# Waveform_Generator_Board.net
KiCad netlist of a schematic drawn in EAGLE
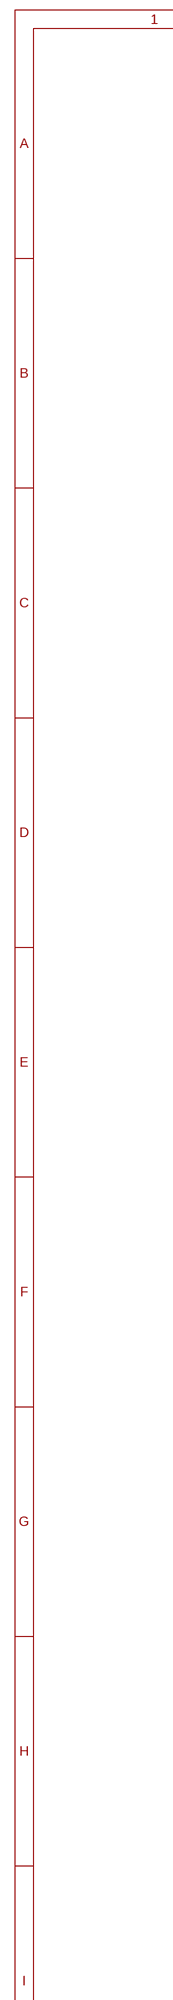
[diagram p0: schematic, sheet 1, part 1 of 2]
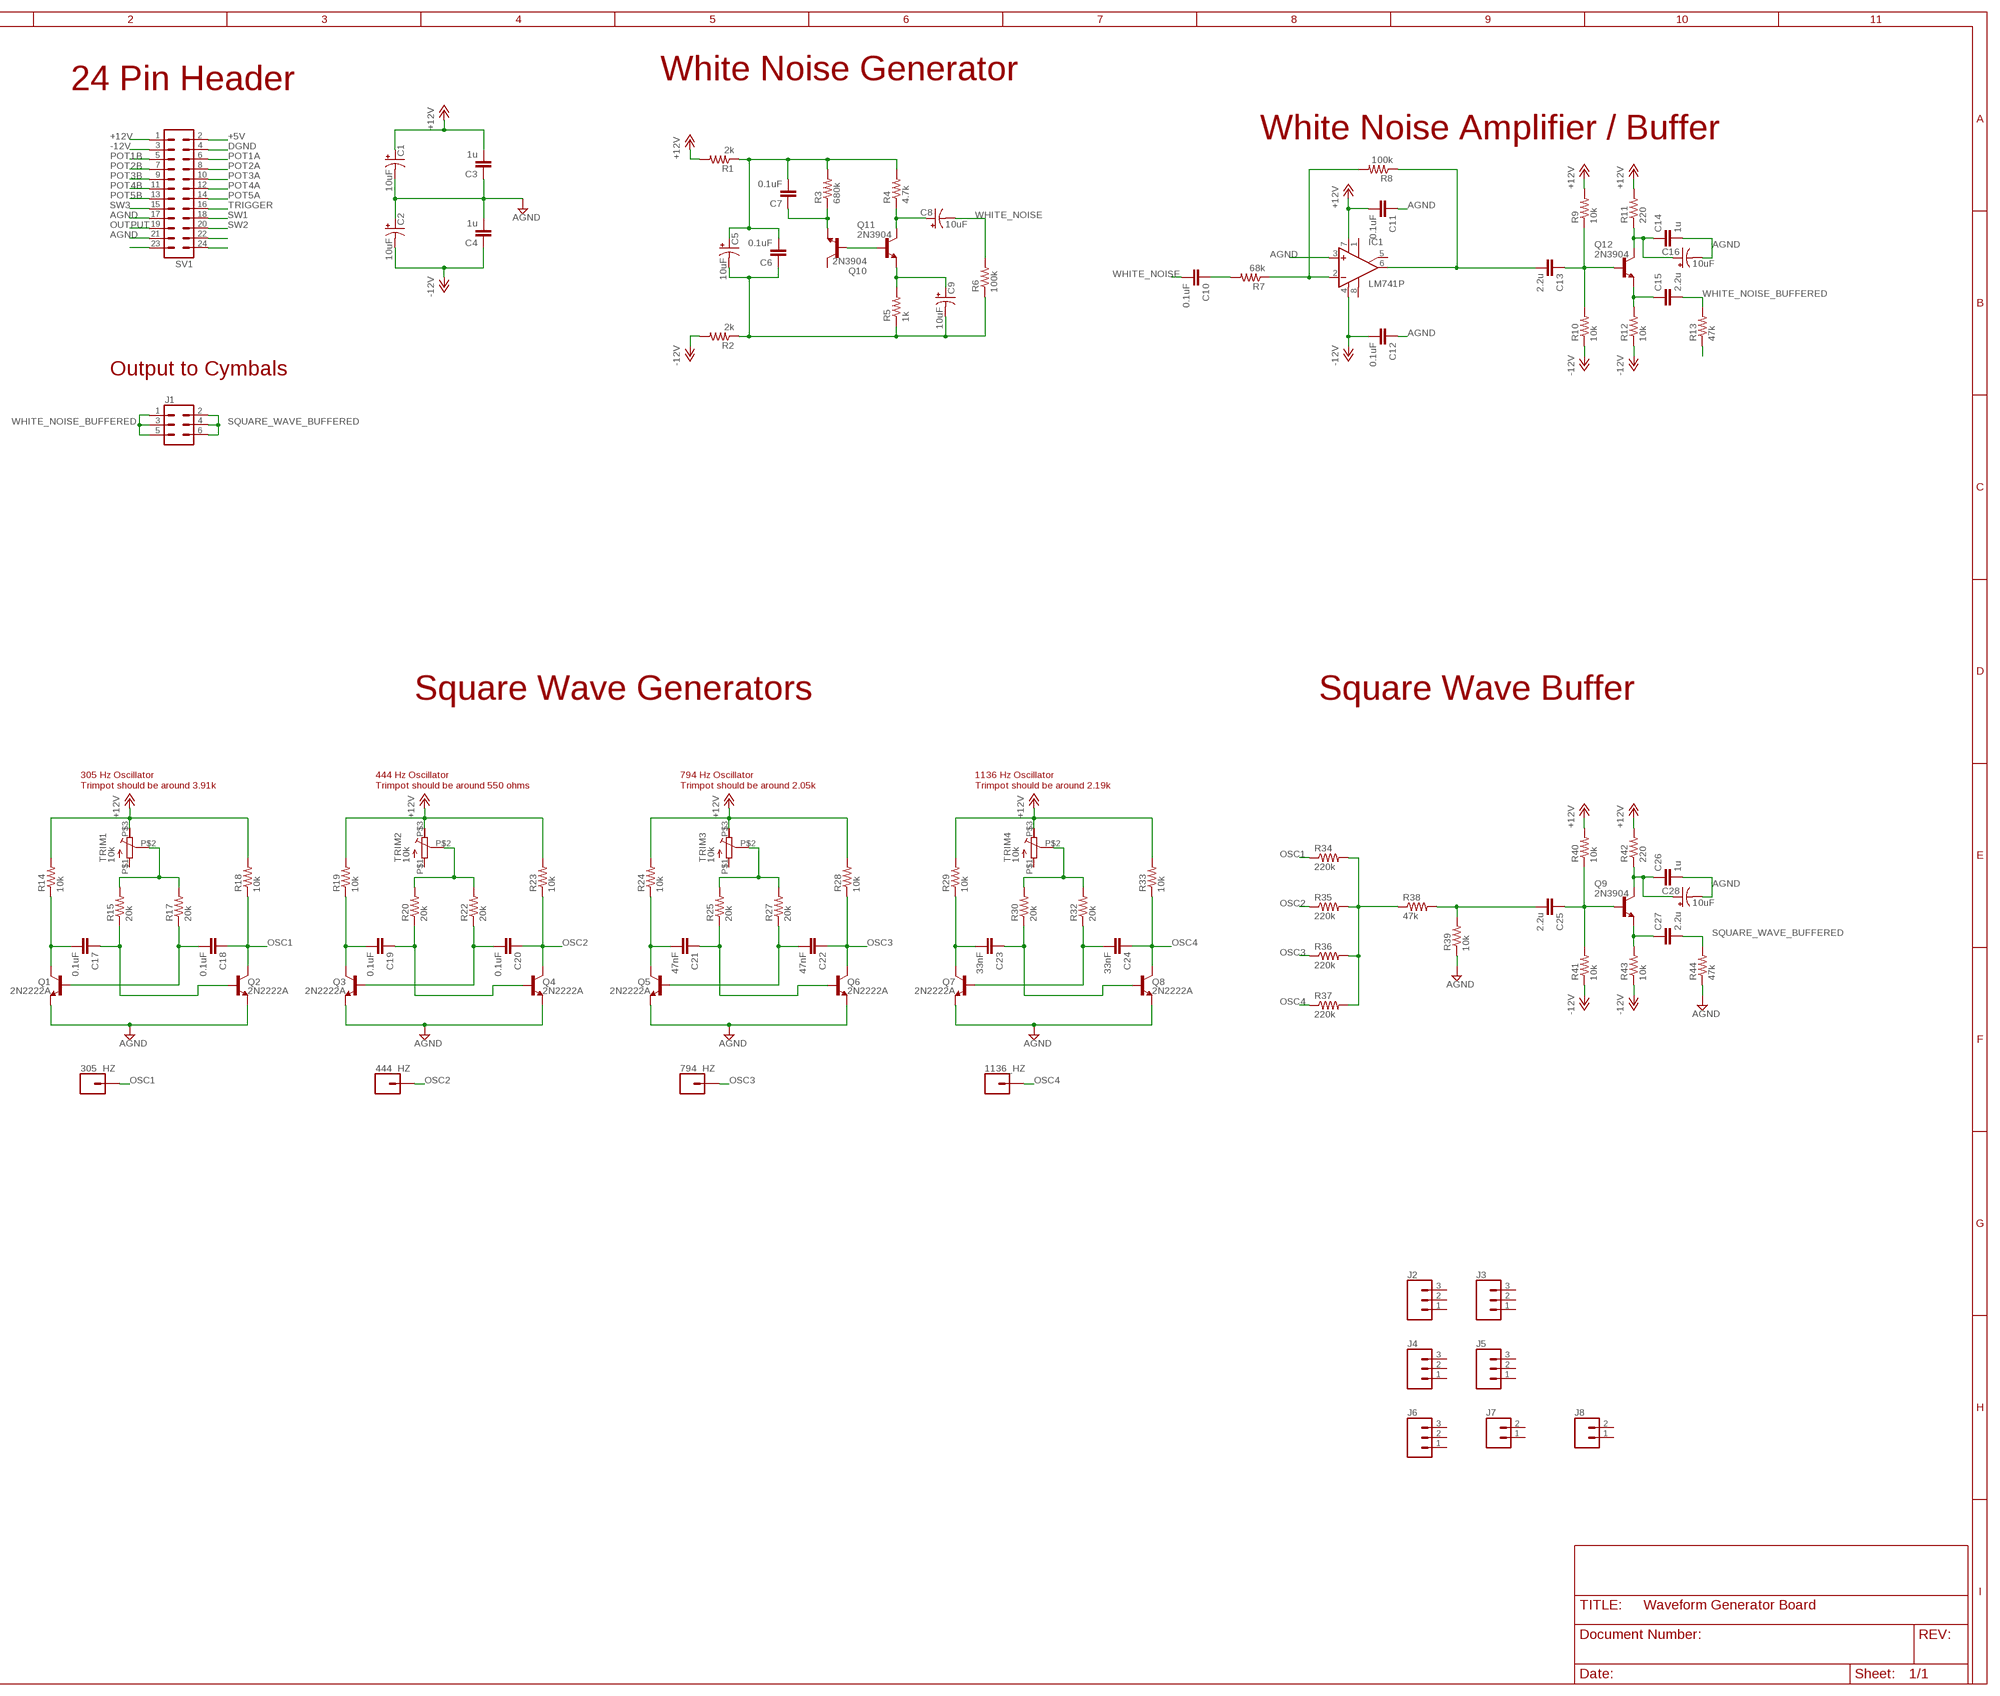
[diagram p1: schematic, sheet 1, part 2 of 2]

(export (version "E")
  (design (tool "Eeschema 10.0.6"))
  (components
    (comp (ref "305_HZ")
      (value "CONN_01PTH_NO_SILK_KIT")
      (footprint "eagle-import:1X01NS_KIT")
      (libsource (lib "eagle-import") (part "CONN_01PTH_NO_SILK_KIT"))
    )
    (comp (ref "444_HZ")
      (value "CONN_01PTH_NO_SILK_KIT")
      (footprint "eagle-import:1X01NS_KIT")
      (libsource (lib "eagle-import") (part "CONN_01PTH_NO_SILK_KIT"))
    )
    (comp (ref "794_HZ")
      (value "CONN_01PTH_NO_SILK_KIT")
      (footprint "eagle-import:1X01NS_KIT")
      (libsource (lib "eagle-import") (part "CONN_01PTH_NO_SILK_KIT"))
    )
    (comp (ref "1136_HZ")
      (value "CONN_01PTH_NO_SILK_KIT")
      (footprint "eagle-import:1X01NS_KIT")
      (libsource (lib "eagle-import") (part "CONN_01PTH_NO_SILK_KIT"))
    )
    (comp (ref "C1")
      (value "10uF")
      (footprint "eagle-import:E2,5-6")
      (libsource (lib "eagle-import") (part "CPOL-USE2.5-6"))
    )
    (comp (ref "C2")
      (value "10uF")
      (footprint "eagle-import:E2,5-6")
      (libsource (lib "eagle-import") (part "CPOL-USE2.5-6"))
    )
    (comp (ref "C3")
      (value "1u")
      (footprint "eagle-import:C050-024X044")
      (libsource (lib "eagle-import") (part "C-EU050-024X044"))
    )
    (comp (ref "C4")
      (value "1u")
      (footprint "eagle-import:C050-024X044")
      (libsource (lib "eagle-import") (part "C-EU050-024X044"))
    )
    (comp (ref "C5")
      (value "10uF")
      (footprint "eagle-import:E2,5-6")
      (libsource (lib "eagle-import") (part "CPOL-USE2.5-6"))
    )
    (comp (ref "C6")
      (value "0.1uF")
      (footprint "eagle-import:C050-024X044")
      (libsource (lib "eagle-import") (part "C-EU050-024X044"))
    )
    (comp (ref "C7")
      (value "0.1uF")
      (footprint "eagle-import:C050-024X044")
      (libsource (lib "eagle-import") (part "C-EU050-024X044"))
    )
    (comp (ref "C8")
      (value "10uF")
      (footprint "eagle-import:E2,5-6")
      (libsource (lib "eagle-import") (part "CPOL-USE2.5-6"))
    )
    (comp (ref "C9")
      (value "10uF")
      (footprint "eagle-import:E2,5-6")
      (libsource (lib "eagle-import") (part "CPOL-USE2.5-6"))
    )
    (comp (ref "C10")
      (value "0.1uF")
      (footprint "eagle-import:C050-024X044")
      (libsource (lib "eagle-import") (part "C-EU050-024X044"))
    )
    (comp (ref "C11")
      (value "0.1uF")
      (footprint "eagle-import:C050-024X044")
      (libsource (lib "eagle-import") (part "C-EU050-024X044"))
    )
    (comp (ref "C12")
      (value "0.1uF")
      (footprint "eagle-import:C050-024X044")
      (libsource (lib "eagle-import") (part "C-EU050-024X044"))
    )
    (comp (ref "C13")
      (value "2.2u")
      (footprint "eagle-import:C050-024X044")
      (libsource (lib "eagle-import") (part "C-EU050-024X044"))
    )
    (comp (ref "C14")
      (value "1u")
      (footprint "eagle-import:C050-024X044")
      (libsource (lib "eagle-import") (part "C-EU050-024X044"))
    )
    (comp (ref "C15")
      (value "2.2u")
      (footprint "eagle-import:C050-024X044")
      (libsource (lib "eagle-import") (part "C-EU050-024X044"))
    )
    (comp (ref "C16")
      (value "10uF")
      (footprint "eagle-import:E2,5-6")
      (libsource (lib "eagle-import") (part "CPOL-USE2.5-6"))
    )
    (comp (ref "C17")
      (value "0.1uF")
      (footprint "eagle-import:C050-024X044")
      (libsource (lib "eagle-import") (part "C-EU050-024X044"))
    )
    (comp (ref "C18")
      (value "0.1uF")
      (footprint "eagle-import:C050-024X044")
      (libsource (lib "eagle-import") (part "C-EU050-024X044"))
    )
    (comp (ref "C19")
      (value "0.1uF")
      (footprint "eagle-import:C050-024X044")
      (libsource (lib "eagle-import") (part "C-EU050-024X044"))
    )
    (comp (ref "C20")
      (value "0.1uF")
      (footprint "eagle-import:C050-024X044")
      (libsource (lib "eagle-import") (part "C-EU050-024X044"))
    )
    (comp (ref "C21")
      (value "47nF")
      (footprint "eagle-import:C050-024X044")
      (libsource (lib "eagle-import") (part "C-EU050-024X044"))
    )
    (comp (ref "C22")
      (value "47nF")
      (footprint "eagle-import:C050-024X044")
      (libsource (lib "eagle-import") (part "C-EU050-024X044"))
    )
    (comp (ref "C23")
      (value "33nF")
      (footprint "eagle-import:C050-024X044")
      (libsource (lib "eagle-import") (part "C-EU050-024X044"))
    )
    (comp (ref "C24")
      (value "33nF")
      (footprint "eagle-import:C050-024X044")
      (libsource (lib "eagle-import") (part "C-EU050-024X044"))
    )
    (comp (ref "C25")
      (value "2.2u")
      (footprint "eagle-import:C050-024X044")
      (libsource (lib "eagle-import") (part "C-EU050-024X044"))
    )
    (comp (ref "C26")
      (value "1u")
      (footprint "eagle-import:C050-024X044")
      (libsource (lib "eagle-import") (part "C-EU050-024X044"))
    )
    (comp (ref "C27")
      (value "2.2u")
      (footprint "eagle-import:C050-024X044")
      (libsource (lib "eagle-import") (part "C-EU050-024X044"))
    )
    (comp (ref "C28")
      (value "10uF")
      (footprint "eagle-import:E2,5-6")
      (libsource (lib "eagle-import") (part "CPOL-USE2.5-6"))
    )
    (comp (ref "IC1")
      (value "LM741P")
      (footprint "eagle-import:DIL08")
      (libsource (lib "eagle-import") (part "741PLM"))
    )
    (comp (ref "J1")
      (value "CONN_03X2NO_SILK")
      (footprint "eagle-import:2X3-NS")
      (libsource (lib "eagle-import") (part "CONN_03X2NO_SILK"))
    )
    (comp (ref "J2")
      (value "CONN_031X03_NO_SILK")
      (footprint "eagle-import:1X03_NO_SILK")
      (libsource (lib "eagle-import") (part "CONN_031X03_NO_SILK"))
    )
    (comp (ref "J3")
      (value "CONN_031X03_NO_SILK")
      (footprint "eagle-import:1X03_NO_SILK")
      (libsource (lib "eagle-import") (part "CONN_031X03_NO_SILK"))
    )
    (comp (ref "J4")
      (value "CONN_031X03_NO_SILK")
      (footprint "eagle-import:1X03_NO_SILK")
      (libsource (lib "eagle-import") (part "CONN_031X03_NO_SILK"))
    )
    (comp (ref "J5")
      (value "CONN_031X03_NO_SILK")
      (footprint "eagle-import:1X03_NO_SILK")
      (libsource (lib "eagle-import") (part "CONN_031X03_NO_SILK"))
    )
    (comp (ref "J6")
      (value "CONN_031X03_NO_SILK")
      (footprint "eagle-import:1X03_NO_SILK")
      (libsource (lib "eagle-import") (part "CONN_031X03_NO_SILK"))
    )
    (comp (ref "J7")
      (value "CONN_021X02_NO_SILK")
      (footprint "eagle-import:1X02_NO_SILK")
      (libsource (lib "eagle-import") (part "CONN_021X02_NO_SILK"))
    )
    (comp (ref "J8")
      (value "CONN_021X02_NO_SILK")
      (footprint "eagle-import:1X02_NO_SILK")
      (libsource (lib "eagle-import") (part "CONN_021X02_NO_SILK"))
    )
    (comp (ref "Q1")
      (value "2N2222A")
      (footprint "eagle-import:TO-92")
      (libsource (lib "eagle-import") (part "TRANS_NPN-P2N2222A"))
    )
    (comp (ref "Q2")
      (value "2N2222A")
      (footprint "eagle-import:TO-92")
      (libsource (lib "eagle-import") (part "TRANS_NPN-P2N2222A"))
    )
    (comp (ref "Q3")
      (value "2N2222A")
      (footprint "eagle-import:TO-92")
      (libsource (lib "eagle-import") (part "TRANS_NPN-P2N2222A"))
    )
    (comp (ref "Q4")
      (value "2N2222A")
      (footprint "eagle-import:TO-92")
      (libsource (lib "eagle-import") (part "TRANS_NPN-P2N2222A"))
    )
    (comp (ref "Q5")
      (value "2N2222A")
      (footprint "eagle-import:TO-92")
      (libsource (lib "eagle-import") (part "TRANS_NPN-P2N2222A"))
    )
    (comp (ref "Q6")
      (value "2N2222A")
      (footprint "eagle-import:TO-92")
      (libsource (lib "eagle-import") (part "TRANS_NPN-P2N2222A"))
    )
    (comp (ref "Q7")
      (value "2N2222A")
      (footprint "eagle-import:TO-92")
      (libsource (lib "eagle-import") (part "TRANS_NPN-P2N2222A"))
    )
    (comp (ref "Q8")
      (value "2N2222A")
      (footprint "eagle-import:TO-92")
      (libsource (lib "eagle-import") (part "TRANS_NPN-P2N2222A"))
    )
    (comp (ref "Q9")
      (value "2N3904")
      (footprint "eagle-import:TO92")
      (libsource (lib "eagle-import") (part "2N3904"))
    )
    (comp (ref "Q10")
      (value "2N3904")
      (footprint "eagle-import:TO92")
      (libsource (lib "eagle-import") (part "2N3904"))
    )
    (comp (ref "Q11")
      (value "2N3904")
      (footprint "eagle-import:TO92")
      (libsource (lib "eagle-import") (part "2N3904"))
    )
    (comp (ref "Q12")
      (value "2N3904")
      (footprint "eagle-import:TO92")
      (libsource (lib "eagle-import") (part "2N3904"))
    )
    (comp (ref "R1")
      (value "2k")
      (footprint "eagle-import:0207_7")
      (libsource (lib "eagle-import") (part "R-US_0207/7"))
    )
    (comp (ref "R2")
      (value "2k")
      (footprint "eagle-import:0207_7")
      (libsource (lib "eagle-import") (part "R-US_0207/7"))
    )
    (comp (ref "R3")
      (value "680k")
      (footprint "eagle-import:0207_7")
      (libsource (lib "eagle-import") (part "R-US_0207/7"))
    )
    (comp (ref "R4")
      (value "4.7k")
      (footprint "eagle-import:0207_7")
      (libsource (lib "eagle-import") (part "R-US_0207/7"))
    )
    (comp (ref "R5")
      (value "1k")
      (footprint "eagle-import:0207_7")
      (libsource (lib "eagle-import") (part "R-US_0207/7"))
    )
    (comp (ref "R6")
      (value "100k")
      (footprint "eagle-import:0207_7")
      (libsource (lib "eagle-import") (part "R-US_0207/7"))
    )
    (comp (ref "R7")
      (value "68k")
      (footprint "eagle-import:0207_7")
      (libsource (lib "eagle-import") (part "R-US_0207/7"))
    )
    (comp (ref "R8")
      (value "100k")
      (footprint "eagle-import:0207_7")
      (libsource (lib "eagle-import") (part "R-US_0207/7"))
    )
    (comp (ref "R9")
      (value "10k")
      (footprint "eagle-import:0207_7")
      (libsource (lib "eagle-import") (part "R-US_0207/7"))
    )
    (comp (ref "R10")
      (value "10k")
      (footprint "eagle-import:0207_7")
      (libsource (lib "eagle-import") (part "R-US_0207/7"))
    )
    (comp (ref "R11")
      (value "220")
      (footprint "eagle-import:0207_7")
      (libsource (lib "eagle-import") (part "R-US_0207/7"))
    )
    (comp (ref "R12")
      (value "10k")
      (footprint "eagle-import:0207_7")
      (libsource (lib "eagle-import") (part "R-US_0207/7"))
    )
    (comp (ref "R13")
      (value "47k")
      (footprint "eagle-import:0207_7")
      (libsource (lib "eagle-import") (part "R-US_0207/7"))
    )
    (comp (ref "R14")
      (value "10k")
      (footprint "eagle-import:0207_7")
      (libsource (lib "eagle-import") (part "R-US_0207/7"))
    )
    (comp (ref "R15")
      (value "20k")
      (footprint "eagle-import:0207_7")
      (libsource (lib "eagle-import") (part "R-US_0207/7"))
    )
    (comp (ref "R17")
      (value "20k")
      (footprint "eagle-import:0207_7")
      (libsource (lib "eagle-import") (part "R-US_0207/7"))
    )
    (comp (ref "R18")
      (value "10k")
      (footprint "eagle-import:0207_7")
      (libsource (lib "eagle-import") (part "R-US_0207/7"))
    )
    (comp (ref "R19")
      (value "10k")
      (footprint "eagle-import:0207_7")
      (libsource (lib "eagle-import") (part "R-US_0207/7"))
    )
    (comp (ref "R20")
      (value "20k")
      (footprint "eagle-import:0207_7")
      (libsource (lib "eagle-import") (part "R-US_0207/7"))
    )
    (comp (ref "R22")
      (value "20k")
      (footprint "eagle-import:0207_7")
      (libsource (lib "eagle-import") (part "R-US_0207/7"))
    )
    (comp (ref "R23")
      (value "10k")
      (footprint "eagle-import:0207_7")
      (libsource (lib "eagle-import") (part "R-US_0207/7"))
    )
    (comp (ref "R24")
      (value "10k")
      (footprint "eagle-import:0207_7")
      (libsource (lib "eagle-import") (part "R-US_0207/7"))
    )
    (comp (ref "R25")
      (value "20k")
      (footprint "eagle-import:0207_7")
      (libsource (lib "eagle-import") (part "R-US_0207/7"))
    )
    (comp (ref "R27")
      (value "20k")
      (footprint "eagle-import:0207_7")
      (libsource (lib "eagle-import") (part "R-US_0207/7"))
    )
    (comp (ref "R28")
      (value "10k")
      (footprint "eagle-import:0207_7")
      (libsource (lib "eagle-import") (part "R-US_0207/7"))
    )
    (comp (ref "R29")
      (value "10k")
      (footprint "eagle-import:0207_7")
      (libsource (lib "eagle-import") (part "R-US_0207/7"))
    )
    (comp (ref "R30")
      (value "20k")
      (footprint "eagle-import:0207_7")
      (libsource (lib "eagle-import") (part "R-US_0207/7"))
    )
    (comp (ref "R32")
      (value "20k")
      (footprint "eagle-import:0207_7")
      (libsource (lib "eagle-import") (part "R-US_0207/7"))
    )
    (comp (ref "R33")
      (value "10k")
      (footprint "eagle-import:0207_7")
      (libsource (lib "eagle-import") (part "R-US_0207/7"))
    )
    (comp (ref "R34")
      (value "220k")
      (footprint "eagle-import:0207_7")
      (libsource (lib "eagle-import") (part "R-US_0207/7"))
    )
    (comp (ref "R35")
      (value "220k")
      (footprint "eagle-import:0207_7")
      (libsource (lib "eagle-import") (part "R-US_0207/7"))
    )
    (comp (ref "R36")
      (value "220k")
      (footprint "eagle-import:0207_7")
      (libsource (lib "eagle-import") (part "R-US_0207/7"))
    )
    (comp (ref "R37")
      (value "220k")
      (footprint "eagle-import:0207_7")
      (libsource (lib "eagle-import") (part "R-US_0207/7"))
    )
    (comp (ref "R38")
      (value "47k")
      (footprint "eagle-import:0207_7")
      (libsource (lib "eagle-import") (part "R-US_0207/7"))
    )
    (comp (ref "R39")
      (value "10k")
      (footprint "eagle-import:0207_7")
      (libsource (lib "eagle-import") (part "R-US_0207/7"))
    )
    (comp (ref "R40")
      (value "10k")
      (footprint "eagle-import:0207_7")
      (libsource (lib "eagle-import") (part "R-US_0207/7"))
    )
    (comp (ref "R41")
      (value "10k")
      (footprint "eagle-import:0207_7")
      (libsource (lib "eagle-import") (part "R-US_0207/7"))
    )
    (comp (ref "R42")
      (value "220")
      (footprint "eagle-import:0207_7")
      (libsource (lib "eagle-import") (part "R-US_0207/7"))
    )
    (comp (ref "R43")
      (value "10k")
      (footprint "eagle-import:0207_7")
      (libsource (lib "eagle-import") (part "R-US_0207/7"))
    )
    (comp (ref "R44")
      (value "47k")
      (footprint "eagle-import:0207_7")
      (libsource (lib "eagle-import") (part "R-US_0207/7"))
    )
    (comp (ref "SV1")
      (value "MA12-2")
      (footprint "eagle-import:MA12-2")
      (libsource (lib "eagle-import") (part "MA12-2"))
    )
    (comp (ref "TRIM1")
      (value "10k")
      (footprint "eagle-import:10K_TRIM")
      (libsource (lib "eagle-import") (part "10K_TRIMMER"))
    )
    (comp (ref "TRIM2")
      (value "10k")
      (footprint "eagle-import:10K_TRIM")
      (libsource (lib "eagle-import") (part "10K_TRIMMER"))
    )
    (comp (ref "TRIM3")
      (value "10k")
      (footprint "eagle-import:10K_TRIM")
      (libsource (lib "eagle-import") (part "10K_TRIMMER"))
    )
    (comp (ref "TRIM4")
      (value "10k")
      (footprint "eagle-import:10K_TRIM")
      (libsource (lib "eagle-import") (part "10K_TRIMMER"))
    )
  )
  (nets
    (net (code "1") (name "+12V") (class "Default")
      (node (ref "C1") (pin "+") (pinfunction "+_+") (pintype "passive"))
      (node (ref "C11") (pin "2") (pinfunction "2_2") (pintype "passive"))
      (node (ref "C3") (pin "2") (pinfunction "2_2") (pintype "passive"))
      (node (ref "IC1") (pin "7") (pinfunction "V+_7") (pintype "power_in"))
      (node (ref "R1") (pin "2") (pinfunction "2_2") (pintype "passive"))
      (node (ref "R11") (pin "2") (pinfunction "2_2") (pintype "passive"))
      (node (ref "R14") (pin "2") (pinfunction "2_2") (pintype "passive"))
      (node (ref "R18") (pin "2") (pinfunction "2_2") (pintype "passive"))
      (node (ref "R19") (pin "2") (pinfunction "2_2") (pintype "passive"))
      (node (ref "R23") (pin "2") (pinfunction "2_2") (pintype "passive"))
      (node (ref "R24") (pin "2") (pinfunction "2_2") (pintype "passive"))
      (node (ref "R28") (pin "2") (pinfunction "2_2") (pintype "passive"))
      (node (ref "R29") (pin "2") (pinfunction "2_2") (pintype "passive"))
      (node (ref "R33") (pin "2") (pinfunction "2_2") (pintype "passive"))
      (node (ref "R40") (pin "2") (pinfunction "2_2") (pintype "passive"))
      (node (ref "R42") (pin "2") (pinfunction "2_2") (pintype "passive"))
      (node (ref "R9") (pin "2") (pinfunction "2_2") (pintype "passive"))
      (node (ref "SV1") (pin "1") (pinfunction "1_1") (pintype "passive"))
      (node (ref "TRIM1") (pin "P$3") (pinfunction "E_P$3") (pintype "passive"))
      (node (ref "TRIM2") (pin "P$3") (pinfunction "E_P$3") (pintype "passive"))
      (node (ref "TRIM3") (pin "P$3") (pinfunction "E_P$3") (pintype "passive"))
      (node (ref "TRIM4") (pin "P$3") (pinfunction "E_P$3") (pintype "passive"))
    )
    (net (code "2") (name "-12V") (class "Default")
      (node (ref "C12") (pin "2") (pinfunction "2_2") (pintype "passive"))
      (node (ref "C2") (pin "-") (pinfunction "-_-") (pintype "passive"))
      (node (ref "C4") (pin "1") (pinfunction "1_1") (pintype "passive"))
      (node (ref "IC1") (pin "4") (pinfunction "V-_4") (pintype "power_in"))
      (node (ref "R10") (pin "1") (pinfunction "1_1") (pintype "passive"))
      (node (ref "R12") (pin "1") (pinfunction "1_1") (pintype "passive"))
      (node (ref "R2") (pin "2") (pinfunction "2_2") (pintype "passive"))
      (node (ref "R41") (pin "1") (pinfunction "1_1") (pintype "passive"))
      (node (ref "R43") (pin "1") (pinfunction "1_1") (pintype "passive"))
      (node (ref "SV1") (pin "3") (pinfunction "3_3") (pintype "passive"))
    )
    (net (code "3") (name "/+5V") (class "Default")
      (node (ref "SV1") (pin "2") (pinfunction "2_2") (pintype "passive"))
    )
    (net (code "4") (name "/DGND") (class "Default")
      (node (ref "SV1") (pin "4") (pinfunction "4_4") (pintype "passive"))
    )
    (net (code "5") (name "/OSC1") (class "Default")
      (node (ref "305_HZ") (pin "1") (pinfunction "1_1") (pintype "passive"))
      (node (ref "C18") (pin "1") (pinfunction "1_1") (pintype "passive"))
      (node (ref "Q2") (pin "1") (pinfunction "C_1") (pintype "passive"))
      (node (ref "R18") (pin "1") (pinfunction "1_1") (pintype "passive"))
      (node (ref "R34") (pin "1") (pinfunction "1_1") (pintype "passive"))
    )
    (net (code "6") (name "/OSC2") (class "Default")
      (node (ref "444_HZ") (pin "1") (pinfunction "1_1") (pintype "passive"))
      (node (ref "C20") (pin "1") (pinfunction "1_1") (pintype "passive"))
      (node (ref "Q4") (pin "1") (pinfunction "C_1") (pintype "passive"))
      (node (ref "R23") (pin "1") (pinfunction "1_1") (pintype "passive"))
      (node (ref "R35") (pin "1") (pinfunction "1_1") (pintype "passive"))
    )
    (net (code "7") (name "/OSC3") (class "Default")
      (node (ref "794_HZ") (pin "1") (pinfunction "1_1") (pintype "passive"))
      (node (ref "C22") (pin "1") (pinfunction "1_1") (pintype "passive"))
      (node (ref "Q6") (pin "1") (pinfunction "C_1") (pintype "passive"))
      (node (ref "R28") (pin "1") (pinfunction "1_1") (pintype "passive"))
      (node (ref "R36") (pin "1") (pinfunction "1_1") (pintype "passive"))
    )
    (net (code "8") (name "/OSC4") (class "Default")
      (node (ref "1136_HZ") (pin "1") (pinfunction "1_1") (pintype "passive"))
      (node (ref "C24") (pin "1") (pinfunction "1_1") (pintype "passive"))
      (node (ref "Q8") (pin "1") (pinfunction "C_1") (pintype "passive"))
      (node (ref "R33") (pin "1") (pinfunction "1_1") (pintype "passive"))
      (node (ref "R37") (pin "1") (pinfunction "1_1") (pintype "passive"))
    )
    (net (code "9") (name "/OUTPUT") (class "Default")
      (node (ref "SV1") (pin "19") (pinfunction "19_19") (pintype "passive"))
    )
    (net (code "10") (name "/POT1A") (class "Default")
      (node (ref "SV1") (pin "6") (pinfunction "6_6") (pintype "passive"))
    )
    (net (code "11") (name "/POT1B") (class "Default")
      (node (ref "SV1") (pin "5") (pinfunction "5_5") (pintype "passive"))
    )
    (net (code "12") (name "/POT2A") (class "Default")
      (node (ref "SV1") (pin "8") (pinfunction "8_8") (pintype "passive"))
    )
    (net (code "13") (name "/POT2B") (class "Default")
      (node (ref "SV1") (pin "7") (pinfunction "7_7") (pintype "passive"))
    )
    (net (code "14") (name "/POT3A") (class "Default")
      (node (ref "SV1") (pin "10") (pinfunction "10_10") (pintype "passive"))
    )
    (net (code "15") (name "/POT3B") (class "Default")
      (node (ref "SV1") (pin "9") (pinfunction "9_9") (pintype "passive"))
    )
    (net (code "16") (name "/POT4A") (class "Default")
      (node (ref "SV1") (pin "12") (pinfunction "12_12") (pintype "passive"))
    )
    (net (code "17") (name "/POT4B") (class "Default")
      (node (ref "SV1") (pin "11") (pinfunction "11_11") (pintype "passive"))
    )
    (net (code "18") (name "/POT5A") (class "Default")
      (node (ref "SV1") (pin "14") (pinfunction "14_14") (pintype "passive"))
    )
    (net (code "19") (name "/POT5B") (class "Default")
      (node (ref "SV1") (pin "13") (pinfunction "13_13") (pintype "passive"))
    )
    (net (code "20") (name "/SQUARE_WAVE_BUFFERED") (class "Default")
      (node (ref "C27") (pin "2") (pinfunction "2_2") (pintype "passive"))
      (node (ref "J1") (pin "2") (pinfunction "2_2") (pintype "bidirectional"))
      (node (ref "J1") (pin "4") (pinfunction "4_4") (pintype "bidirectional"))
      (node (ref "J1") (pin "6") (pinfunction "6_6") (pintype "bidirectional"))
      (node (ref "R44") (pin "2") (pinfunction "2_2") (pintype "passive"))
    )
    (net (code "21") (name "/SW1") (class "Default")
      (node (ref "SV1") (pin "18") (pinfunction "18_18") (pintype "passive"))
    )
    (net (code "22") (name "/SW2") (class "Default")
      (node (ref "SV1") (pin "20") (pinfunction "20_20") (pintype "passive"))
    )
    (net (code "23") (name "/SW3") (class "Default")
      (node (ref "SV1") (pin "15") (pinfunction "15_15") (pintype "passive"))
    )
    (net (code "24") (name "/TRIGGER") (class "Default")
      (node (ref "SV1") (pin "16") (pinfunction "16_16") (pintype "passive"))
    )
    (net (code "25") (name "/WHITE_NOISE") (class "Default")
      (node (ref "C10") (pin "2") (pinfunction "2_2") (pintype "passive"))
      (node (ref "C8") (pin "-") (pinfunction "-_-") (pintype "passive"))
      (node (ref "R6") (pin "2") (pinfunction "2_2") (pintype "passive"))
    )
    (net (code "26") (name "/WHITE_NOISE_BUFFERED") (class "Default")
      (node (ref "C15") (pin "2") (pinfunction "2_2") (pintype "passive"))
      (node (ref "J1") (pin "1") (pinfunction "1_1") (pintype "bidirectional"))
      (node (ref "J1") (pin "3") (pinfunction "3_3") (pintype "bidirectional"))
      (node (ref "J1") (pin "5") (pinfunction "5_5") (pintype "bidirectional"))
      (node (ref "R13") (pin "2") (pinfunction "2_2") (pintype "passive"))
    )
    (net (code "27") (name "AGND") (class "Default")
      (node (ref "C1") (pin "-") (pinfunction "-_-") (pintype "passive"))
      (node (ref "C11") (pin "1") (pinfunction "1_1") (pintype "passive"))
      (node (ref "C12") (pin "1") (pinfunction "1_1") (pintype "passive"))
      (node (ref "C14") (pin "2") (pinfunction "2_2") (pintype "passive"))
      (node (ref "C16") (pin "-") (pinfunction "-_-") (pintype "passive"))
      (node (ref "C2") (pin "+") (pinfunction "+_+") (pintype "passive"))
      (node (ref "C26") (pin "2") (pinfunction "2_2") (pintype "passive"))
      (node (ref "C28") (pin "-") (pinfunction "-_-") (pintype "passive"))
      (node (ref "C3") (pin "1") (pinfunction "1_1") (pintype "passive"))
      (node (ref "C4") (pin "2") (pinfunction "2_2") (pintype "passive"))
      (node (ref "IC1") (pin "3") (pinfunction "+IN_3") (pintype "input"))
      (node (ref "Q1") (pin "3") (pinfunction "E_3") (pintype "passive"))
      (node (ref "Q2") (pin "3") (pinfunction "E_3") (pintype "passive"))
      (node (ref "Q3") (pin "3") (pinfunction "E_3") (pintype "passive"))
      (node (ref "Q4") (pin "3") (pinfunction "E_3") (pintype "passive"))
      (node (ref "Q5") (pin "3") (pinfunction "E_3") (pintype "passive"))
      (node (ref "Q6") (pin "3") (pinfunction "E_3") (pintype "passive"))
      (node (ref "Q7") (pin "3") (pinfunction "E_3") (pintype "passive"))
      (node (ref "Q8") (pin "3") (pinfunction "E_3") (pintype "passive"))
      (node (ref "R13") (pin "1") (pinfunction "1_1") (pintype "passive"))
      (node (ref "R39") (pin "1") (pinfunction "1_1") (pintype "passive"))
      (node (ref "R44") (pin "1") (pinfunction "1_1") (pintype "passive"))
      (node (ref "SV1") (pin "17") (pinfunction "17_17") (pintype "passive"))
      (node (ref "SV1") (pin "21") (pinfunction "21_21") (pintype "passive"))
    )
    (net (code "28") (name "Net-(C5-Pad+)") (class "Default")
      (node (ref "C5") (pin "+") (pinfunction "+_+") (pintype "passive"))
      (node (ref "C6") (pin "2") (pinfunction "2_2") (pintype "passive"))
      (node (ref "C7") (pin "2") (pinfunction "2_2") (pintype "passive"))
      (node (ref "R1") (pin "1") (pinfunction "1_1") (pintype "passive"))
      (node (ref "R3") (pin "2") (pinfunction "2_2") (pintype "passive"))
      (node (ref "R4") (pin "2") (pinfunction "2_2") (pintype "passive"))
    )
    (net (code "29") (name "Net-(C5-Pad-)") (class "Default")
      (node (ref "C5") (pin "-") (pinfunction "-_-") (pintype "passive"))
      (node (ref "C6") (pin "1") (pinfunction "1_1") (pintype "passive"))
      (node (ref "C9") (pin "-") (pinfunction "-_-") (pintype "passive"))
      (node (ref "R2") (pin "1") (pinfunction "1_1") (pintype "passive"))
      (node (ref "R5") (pin "1") (pinfunction "1_1") (pintype "passive"))
      (node (ref "R6") (pin "1") (pinfunction "1_1") (pintype "passive"))
    )
    (net (code "30") (name "Net-(C10-Pad1)") (class "Default")
      (node (ref "C10") (pin "1") (pinfunction "1_1") (pintype "passive"))
      (node (ref "R7") (pin "2") (pinfunction "2_2") (pintype "passive"))
    )
    (net (code "31") (name "Net-(C25-Pad2)") (class "Default")
      (node (ref "C25") (pin "2") (pinfunction "2_2") (pintype "passive"))
      (node (ref "R38") (pin "2") (pinfunction "2_2") (pintype "passive"))
      (node (ref "R39") (pin "2") (pinfunction "2_2") (pintype "passive"))
    )
    (net (code "32") (name "Net-(IC1--IN)") (class "Default")
      (node (ref "IC1") (pin "2") (pinfunction "-IN_2") (pintype "input"))
      (node (ref "R7") (pin "1") (pinfunction "1_1") (pintype "passive"))
      (node (ref "R8") (pin "2") (pinfunction "2_2") (pintype "passive"))
    )
    (net (code "33") (name "Net-(IC1-OUT)") (class "Default")
      (node (ref "C13") (pin "2") (pinfunction "2_2") (pintype "passive"))
      (node (ref "IC1") (pin "6") (pinfunction "OUT_6") (pintype "output"))
      (node (ref "R8") (pin "1") (pinfunction "1_1") (pintype "passive"))
    )
    (net (code "34") (name "Net-(Q1-B)") (class "Default")
      (node (ref "C18") (pin "2") (pinfunction "2_2") (pintype "passive"))
      (node (ref "Q1") (pin "2") (pinfunction "B_2") (pintype "passive"))
      (node (ref "R17") (pin "1") (pinfunction "1_1") (pintype "passive"))
    )
    (net (code "35") (name "Net-(Q1-C)") (class "Default")
      (node (ref "C17") (pin "2") (pinfunction "2_2") (pintype "passive"))
      (node (ref "Q1") (pin "1") (pinfunction "C_1") (pintype "passive"))
      (node (ref "R14") (pin "1") (pinfunction "1_1") (pintype "passive"))
    )
    (net (code "36") (name "Net-(Q2-B)") (class "Default")
      (node (ref "C17") (pin "1") (pinfunction "1_1") (pintype "passive"))
      (node (ref "Q2") (pin "2") (pinfunction "B_2") (pintype "passive"))
      (node (ref "R15") (pin "1") (pinfunction "1_1") (pintype "passive"))
    )
    (net (code "37") (name "Net-(Q3-B)") (class "Default")
      (node (ref "C20") (pin "2") (pinfunction "2_2") (pintype "passive"))
      (node (ref "Q3") (pin "2") (pinfunction "B_2") (pintype "passive"))
      (node (ref "R22") (pin "1") (pinfunction "1_1") (pintype "passive"))
    )
    (net (code "38") (name "Net-(Q3-C)") (class "Default")
      (node (ref "C19") (pin "2") (pinfunction "2_2") (pintype "passive"))
      (node (ref "Q3") (pin "1") (pinfunction "C_1") (pintype "passive"))
      (node (ref "R19") (pin "1") (pinfunction "1_1") (pintype "passive"))
    )
    (net (code "39") (name "Net-(Q4-B)") (class "Default")
      (node (ref "C19") (pin "1") (pinfunction "1_1") (pintype "passive"))
      (node (ref "Q4") (pin "2") (pinfunction "B_2") (pintype "passive"))
      (node (ref "R20") (pin "1") (pinfunction "1_1") (pintype "passive"))
    )
    (net (code "40") (name "Net-(Q5-B)") (class "Default")
      (node (ref "C22") (pin "2") (pinfunction "2_2") (pintype "passive"))
      (node (ref "Q5") (pin "2") (pinfunction "B_2") (pintype "passive"))
      (node (ref "R27") (pin "1") (pinfunction "1_1") (pintype "passive"))
    )
    (net (code "41") (name "Net-(Q5-C)") (class "Default")
      (node (ref "C21") (pin "2") (pinfunction "2_2") (pintype "passive"))
      (node (ref "Q5") (pin "1") (pinfunction "C_1") (pintype "passive"))
      (node (ref "R24") (pin "1") (pinfunction "1_1") (pintype "passive"))
    )
    (net (code "42") (name "Net-(Q6-B)") (class "Default")
      (node (ref "C21") (pin "1") (pinfunction "1_1") (pintype "passive"))
      (node (ref "Q6") (pin "2") (pinfunction "B_2") (pintype "passive"))
      (node (ref "R25") (pin "1") (pinfunction "1_1") (pintype "passive"))
    )
    (net (code "43") (name "Net-(Q7-B)") (class "Default")
      (node (ref "C24") (pin "2") (pinfunction "2_2") (pintype "passive"))
      (node (ref "Q7") (pin "2") (pinfunction "B_2") (pintype "passive"))
      (node (ref "R32") (pin "1") (pinfunction "1_1") (pintype "passive"))
    )
    (net (code "44") (name "Net-(Q7-C)") (class "Default")
      (node (ref "C23") (pin "2") (pinfunction "2_2") (pintype "passive"))
      (node (ref "Q7") (pin "1") (pinfunction "C_1") (pintype "passive"))
      (node (ref "R29") (pin "1") (pinfunction "1_1") (pintype "passive"))
    )
    (net (code "45") (name "Net-(Q8-B)") (class "Default")
      (node (ref "C23") (pin "1") (pinfunction "1_1") (pintype "passive"))
      (node (ref "Q8") (pin "2") (pinfunction "B_2") (pintype "passive"))
      (node (ref "R30") (pin "1") (pinfunction "1_1") (pintype "passive"))
    )
    (net (code "46") (name "Net-(Q9-B)") (class "Default")
      (node (ref "C25") (pin "1") (pinfunction "1_1") (pintype "passive"))
      (node (ref "Q9") (pin "2") (pinfunction "B_2") (pintype "passive"))
      (node (ref "R40") (pin "1") (pinfunction "1_1") (pintype "passive"))
      (node (ref "R41") (pin "2") (pinfunction "2_2") (pintype "passive"))
    )
    (net (code "47") (name "Net-(Q9-C)") (class "Default")
      (node (ref "C26") (pin "1") (pinfunction "1_1") (pintype "passive"))
      (node (ref "C28") (pin "+") (pinfunction "+_+") (pintype "passive"))
      (node (ref "Q9") (pin "1") (pinfunction "C_1") (pintype "passive"))
      (node (ref "R42") (pin "1") (pinfunction "1_1") (pintype "passive"))
    )
    (net (code "48") (name "Net-(Q9-E)") (class "Default")
      (node (ref "C27") (pin "1") (pinfunction "1_1") (pintype "passive"))
      (node (ref "Q9") (pin "3") (pinfunction "E_3") (pintype "passive"))
      (node (ref "R43") (pin "2") (pinfunction "2_2") (pintype "passive"))
    )
    (net (code "49") (name "Net-(Q10-B)") (class "Default")
      (node (ref "Q10") (pin "2") (pinfunction "B_2") (pintype "passive"))
      (node (ref "Q11") (pin "2") (pinfunction "B_2") (pintype "passive"))
    )
    (net (code "50") (name "Net-(Q10-E)") (class "Default")
      (node (ref "C7") (pin "1") (pinfunction "1_1") (pintype "passive"))
      (node (ref "Q10") (pin "3") (pinfunction "E_3") (pintype "passive"))
      (node (ref "R3") (pin "1") (pinfunction "1_1") (pintype "passive"))
    )
    (net (code "51") (name "Net-(Q11-C)") (class "Default")
      (node (ref "C8") (pin "+") (pinfunction "+_+") (pintype "passive"))
      (node (ref "Q11") (pin "1") (pinfunction "C_1") (pintype "passive"))
      (node (ref "R4") (pin "1") (pinfunction "1_1") (pintype "passive"))
    )
    (net (code "52") (name "Net-(Q11-E)") (class "Default")
      (node (ref "C9") (pin "+") (pinfunction "+_+") (pintype "passive"))
      (node (ref "Q11") (pin "3") (pinfunction "E_3") (pintype "passive"))
      (node (ref "R5") (pin "2") (pinfunction "2_2") (pintype "passive"))
    )
    (net (code "53") (name "Net-(Q12-B)") (class "Default")
      (node (ref "C13") (pin "1") (pinfunction "1_1") (pintype "passive"))
      (node (ref "Q12") (pin "2") (pinfunction "B_2") (pintype "passive"))
      (node (ref "R10") (pin "2") (pinfunction "2_2") (pintype "passive"))
      (node (ref "R9") (pin "1") (pinfunction "1_1") (pintype "passive"))
    )
    (net (code "54") (name "Net-(Q12-C)") (class "Default")
      (node (ref "C14") (pin "1") (pinfunction "1_1") (pintype "passive"))
      (node (ref "C16") (pin "+") (pinfunction "+_+") (pintype "passive"))
      (node (ref "Q12") (pin "1") (pinfunction "C_1") (pintype "passive"))
      (node (ref "R11") (pin "1") (pinfunction "1_1") (pintype "passive"))
    )
    (net (code "55") (name "Net-(Q12-E)") (class "Default")
      (node (ref "C15") (pin "1") (pinfunction "1_1") (pintype "passive"))
      (node (ref "Q12") (pin "3") (pinfunction "E_3") (pintype "passive"))
      (node (ref "R12") (pin "2") (pinfunction "2_2") (pintype "passive"))
    )
    (net (code "56") (name "Net-(R34-Pad2)") (class "Default")
      (node (ref "R34") (pin "2") (pinfunction "2_2") (pintype "passive"))
      (node (ref "R35") (pin "2") (pinfunction "2_2") (pintype "passive"))
      (node (ref "R36") (pin "2") (pinfunction "2_2") (pintype "passive"))
      (node (ref "R37") (pin "2") (pinfunction "2_2") (pintype "passive"))
      (node (ref "R38") (pin "1") (pinfunction "1_1") (pintype "passive"))
    )
    (net (code "57") (name "Net-(TRIM1-S)") (class "Default")
      (node (ref "R15") (pin "2") (pinfunction "2_2") (pintype "passive"))
      (node (ref "R17") (pin "2") (pinfunction "2_2") (pintype "passive"))
      (node (ref "TRIM1") (pin "P$2") (pinfunction "S_P$2") (pintype "passive"))
    )
    (net (code "58") (name "Net-(TRIM2-S)") (class "Default")
      (node (ref "R20") (pin "2") (pinfunction "2_2") (pintype "passive"))
      (node (ref "R22") (pin "2") (pinfunction "2_2") (pintype "passive"))
      (node (ref "TRIM2") (pin "P$2") (pinfunction "S_P$2") (pintype "passive"))
    )
    (net (code "59") (name "Net-(TRIM3-S)") (class "Default")
      (node (ref "R25") (pin "2") (pinfunction "2_2") (pintype "passive"))
      (node (ref "R27") (pin "2") (pinfunction "2_2") (pintype "passive"))
      (node (ref "TRIM3") (pin "P$2") (pinfunction "S_P$2") (pintype "passive"))
    )
    (net (code "60") (name "Net-(TRIM4-S)") (class "Default")
      (node (ref "R30") (pin "2") (pinfunction "2_2") (pintype "passive"))
      (node (ref "R32") (pin "2") (pinfunction "2_2") (pintype "passive"))
      (node (ref "TRIM4") (pin "P$2") (pinfunction "S_P$2") (pintype "passive"))
    )
    (net (code "61") (name "unconnected-(IC1-ON1-Pad1)") (class "Default")
      (node (ref "IC1") (pin "1") (pinfunction "ON1_1") (pintype "passive"))
    )
    (net (code "62") (name "unconnected-(IC1-ON2-Pad5)") (class "Default")
      (node (ref "IC1") (pin "5") (pinfunction "ON2_5") (pintype "passive"))
    )
    (net (code "63") (name "unconnected-(IC1-OPT-Pad8)") (class "Default")
      (node (ref "IC1") (pin "8") (pinfunction "OPT_8") (pintype "passive"))
    )
    (net (code "64") (name "unconnected-(J2-Pad1)") (class "Default")
      (node (ref "J2") (pin "1") (pinfunction "1_1") (pintype "passive"))
    )
    (net (code "65") (name "unconnected-(J2-Pad2)") (class "Default")
      (node (ref "J2") (pin "2") (pinfunction "2_2") (pintype "passive"))
    )
    (net (code "66") (name "unconnected-(J2-Pad3)") (class "Default")
      (node (ref "J2") (pin "3") (pinfunction "3_3") (pintype "passive"))
    )
    (net (code "67") (name "unconnected-(J3-Pad1)") (class "Default")
      (node (ref "J3") (pin "1") (pinfunction "1_1") (pintype "passive"))
    )
    (net (code "68") (name "unconnected-(J3-Pad2)") (class "Default")
      (node (ref "J3") (pin "2") (pinfunction "2_2") (pintype "passive"))
    )
    (net (code "69") (name "unconnected-(J3-Pad3)") (class "Default")
      (node (ref "J3") (pin "3") (pinfunction "3_3") (pintype "passive"))
    )
    (net (code "70") (name "unconnected-(J4-Pad1)") (class "Default")
      (node (ref "J4") (pin "1") (pinfunction "1_1") (pintype "passive"))
    )
    (net (code "71") (name "unconnected-(J4-Pad2)") (class "Default")
      (node (ref "J4") (pin "2") (pinfunction "2_2") (pintype "passive"))
    )
    (net (code "72") (name "unconnected-(J4-Pad3)") (class "Default")
      (node (ref "J4") (pin "3") (pinfunction "3_3") (pintype "passive"))
    )
    (net (code "73") (name "unconnected-(J5-Pad1)") (class "Default")
      (node (ref "J5") (pin "1") (pinfunction "1_1") (pintype "passive"))
    )
    (net (code "74") (name "unconnected-(J5-Pad2)") (class "Default")
      (node (ref "J5") (pin "2") (pinfunction "2_2") (pintype "passive"))
    )
    (net (code "75") (name "unconnected-(J5-Pad3)") (class "Default")
      (node (ref "J5") (pin "3") (pinfunction "3_3") (pintype "passive"))
    )
    (net (code "76") (name "unconnected-(J6-Pad1)") (class "Default")
      (node (ref "J6") (pin "1") (pinfunction "1_1") (pintype "passive"))
    )
    (net (code "77") (name "unconnected-(J6-Pad2)") (class "Default")
      (node (ref "J6") (pin "2") (pinfunction "2_2") (pintype "passive"))
    )
    (net (code "78") (name "unconnected-(J6-Pad3)") (class "Default")
      (node (ref "J6") (pin "3") (pinfunction "3_3") (pintype "passive"))
    )
    (net (code "79") (name "unconnected-(J7-Pad1)") (class "Default")
      (node (ref "J7") (pin "1") (pinfunction "1_1") (pintype "passive"))
    )
    (net (code "80") (name "unconnected-(J7-Pad2)") (class "Default")
      (node (ref "J7") (pin "2") (pinfunction "2_2") (pintype "passive"))
    )
    (net (code "81") (name "unconnected-(J8-Pad1)") (class "Default")
      (node (ref "J8") (pin "1") (pinfunction "1_1") (pintype "passive"))
    )
    (net (code "82") (name "unconnected-(J8-Pad2)") (class "Default")
      (node (ref "J8") (pin "2") (pinfunction "2_2") (pintype "passive"))
    )
    (net (code "83") (name "unconnected-(Q10-C-Pad1)") (class "Default")
      (node (ref "Q10") (pin "1") (pinfunction "C_1") (pintype "passive"))
    )
    (net (code "84") (name "unconnected-(SV1-Pad22)") (class "Default")
      (node (ref "SV1") (pin "22") (pinfunction "22_22") (pintype "passive"))
    )
    (net (code "85") (name "unconnected-(SV1-Pad23)") (class "Default")
      (node (ref "SV1") (pin "23") (pinfunction "23_23") (pintype "passive"))
    )
    (net (code "86") (name "unconnected-(SV1-Pad24)") (class "Default")
      (node (ref "SV1") (pin "24") (pinfunction "24_24") (pintype "passive"))
    )
    (net (code "87") (name "unconnected-(TRIM1-A-PadP$1)") (class "Default")
      (node (ref "TRIM1") (pin "P$1") (pinfunction "A_P$1") (pintype "passive"))
    )
    (net (code "88") (name "unconnected-(TRIM2-A-PadP$1)") (class "Default")
      (node (ref "TRIM2") (pin "P$1") (pinfunction "A_P$1") (pintype "passive"))
    )
    (net (code "89") (name "unconnected-(TRIM3-A-PadP$1)") (class "Default")
      (node (ref "TRIM3") (pin "P$1") (pinfunction "A_P$1") (pintype "passive"))
    )
    (net (code "90") (name "unconnected-(TRIM4-A-PadP$1)") (class "Default")
      (node (ref "TRIM4") (pin "P$1") (pinfunction "A_P$1") (pintype "passive"))
    )
  )
)
